# Power_Amp_carlos_2.net
KiCad netlist of a schematic drawn in EAGLE
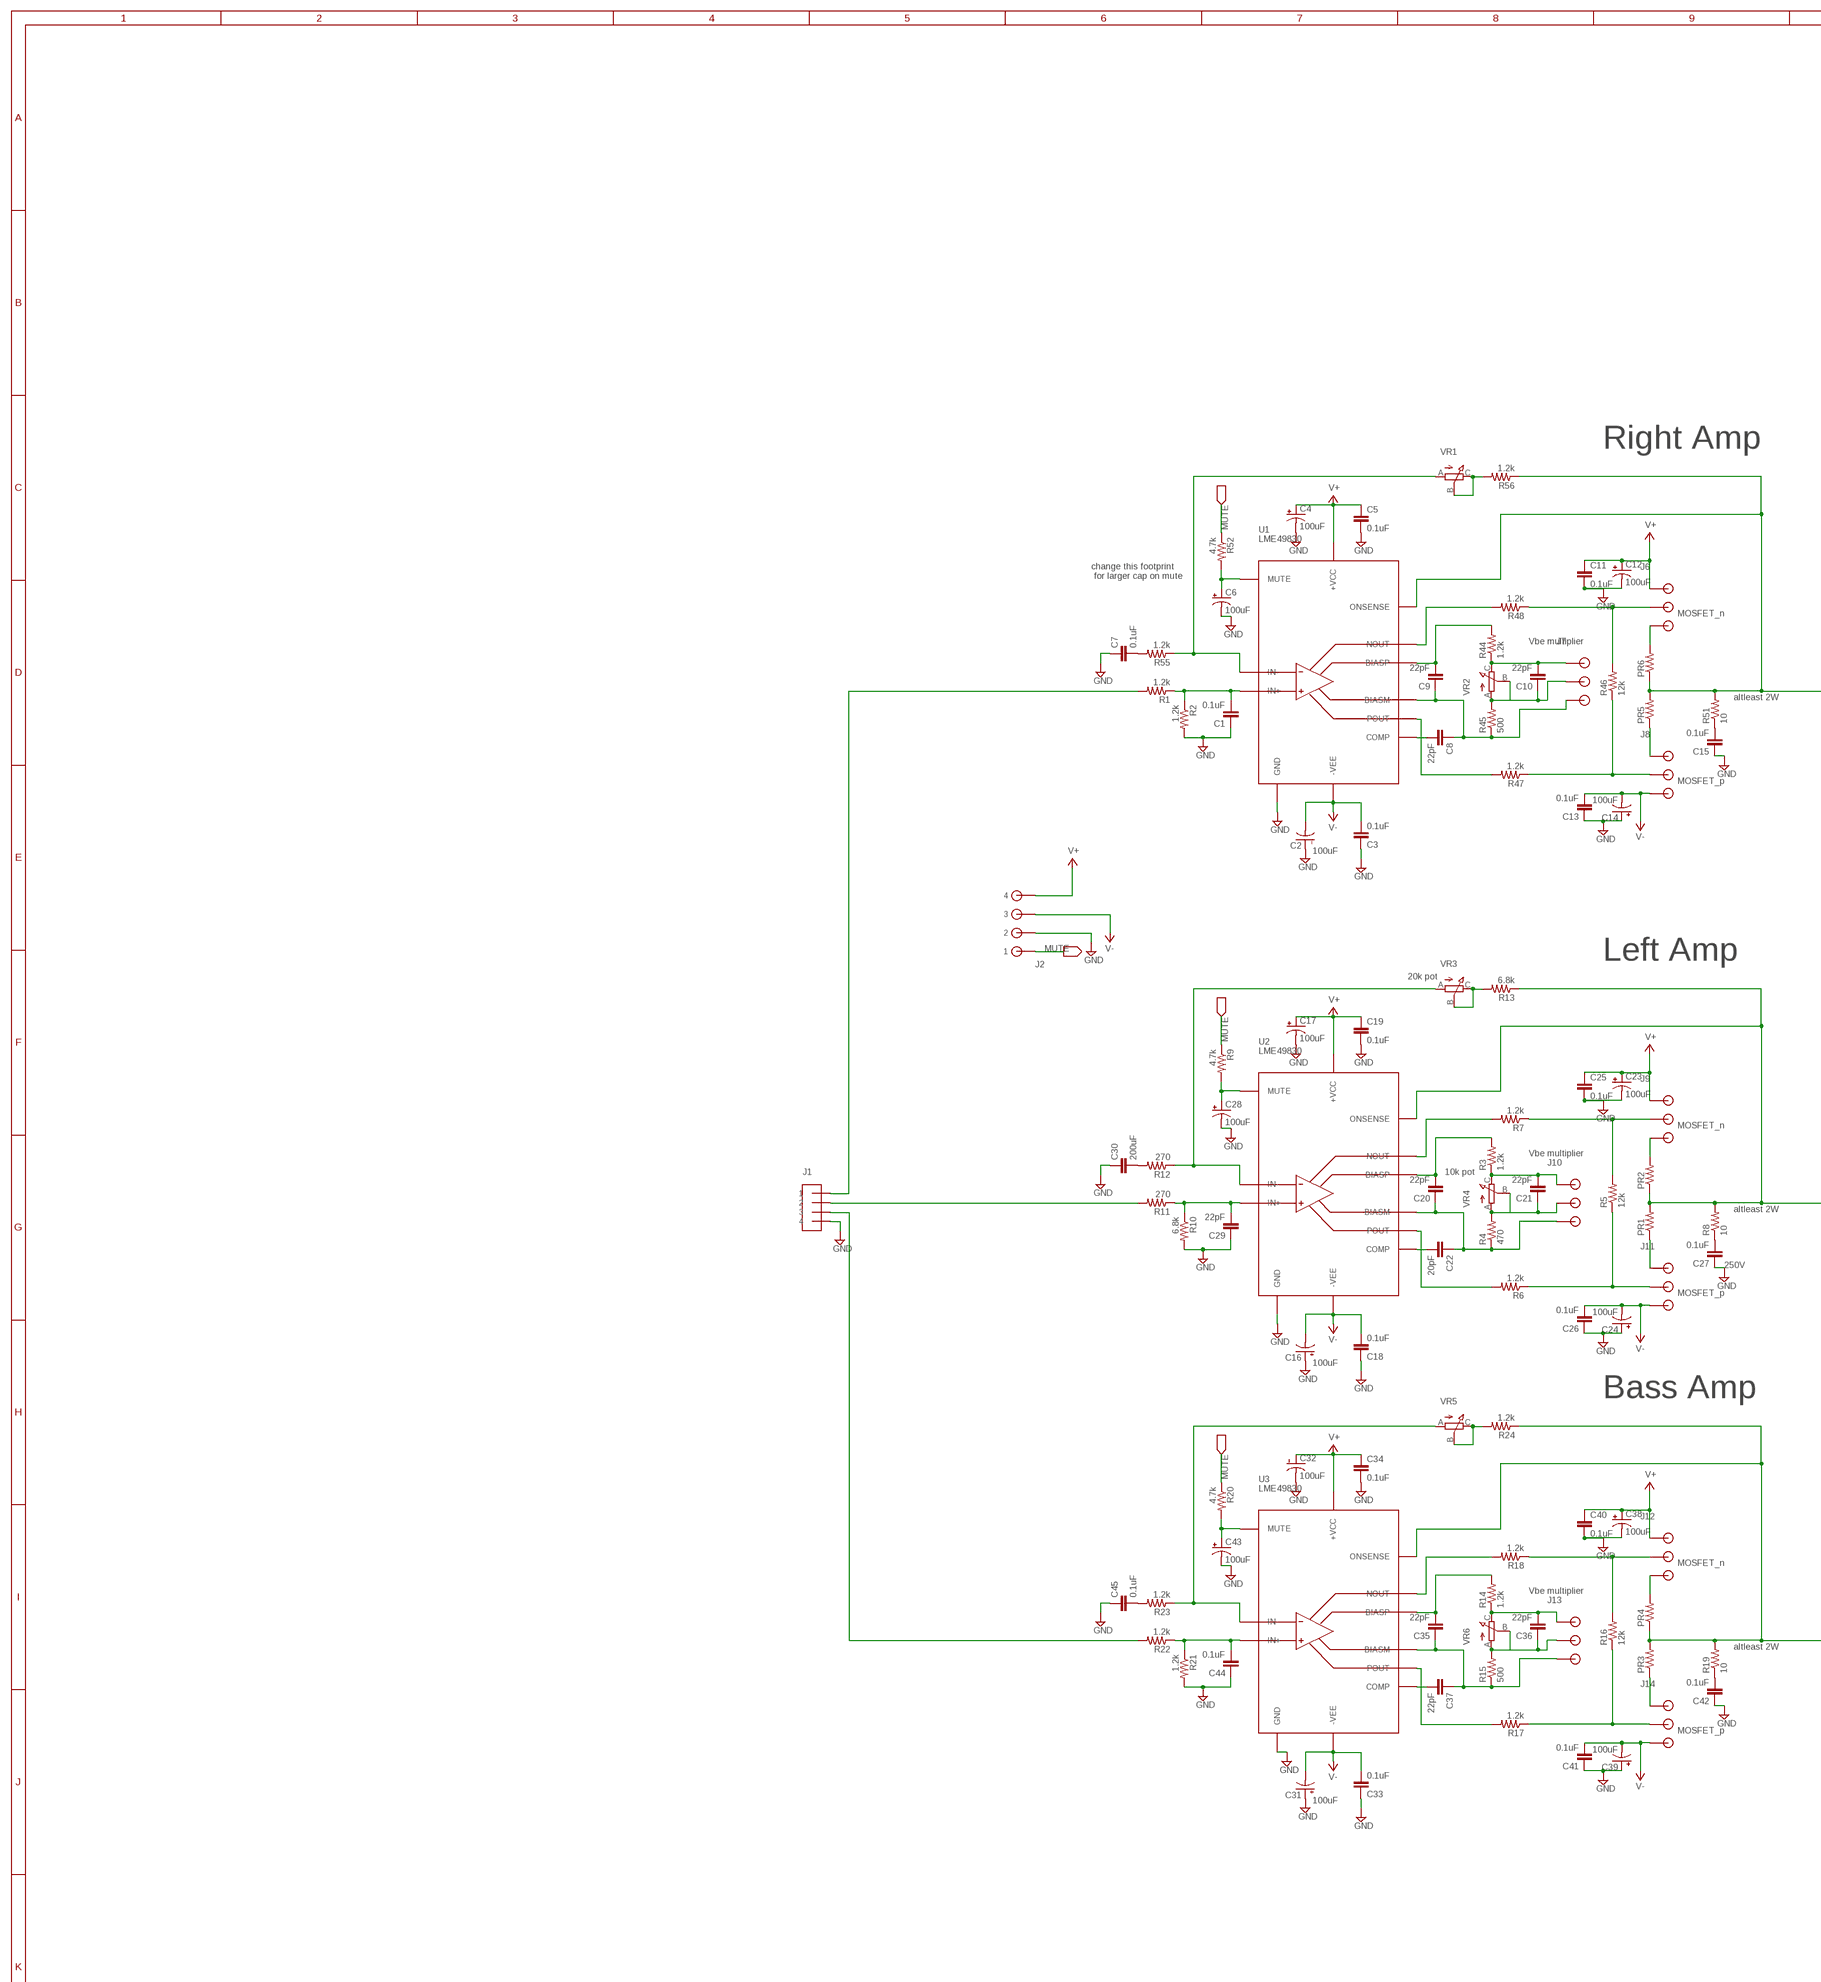
[diagram p0: schematic, sheet 1, part 1 of 3]
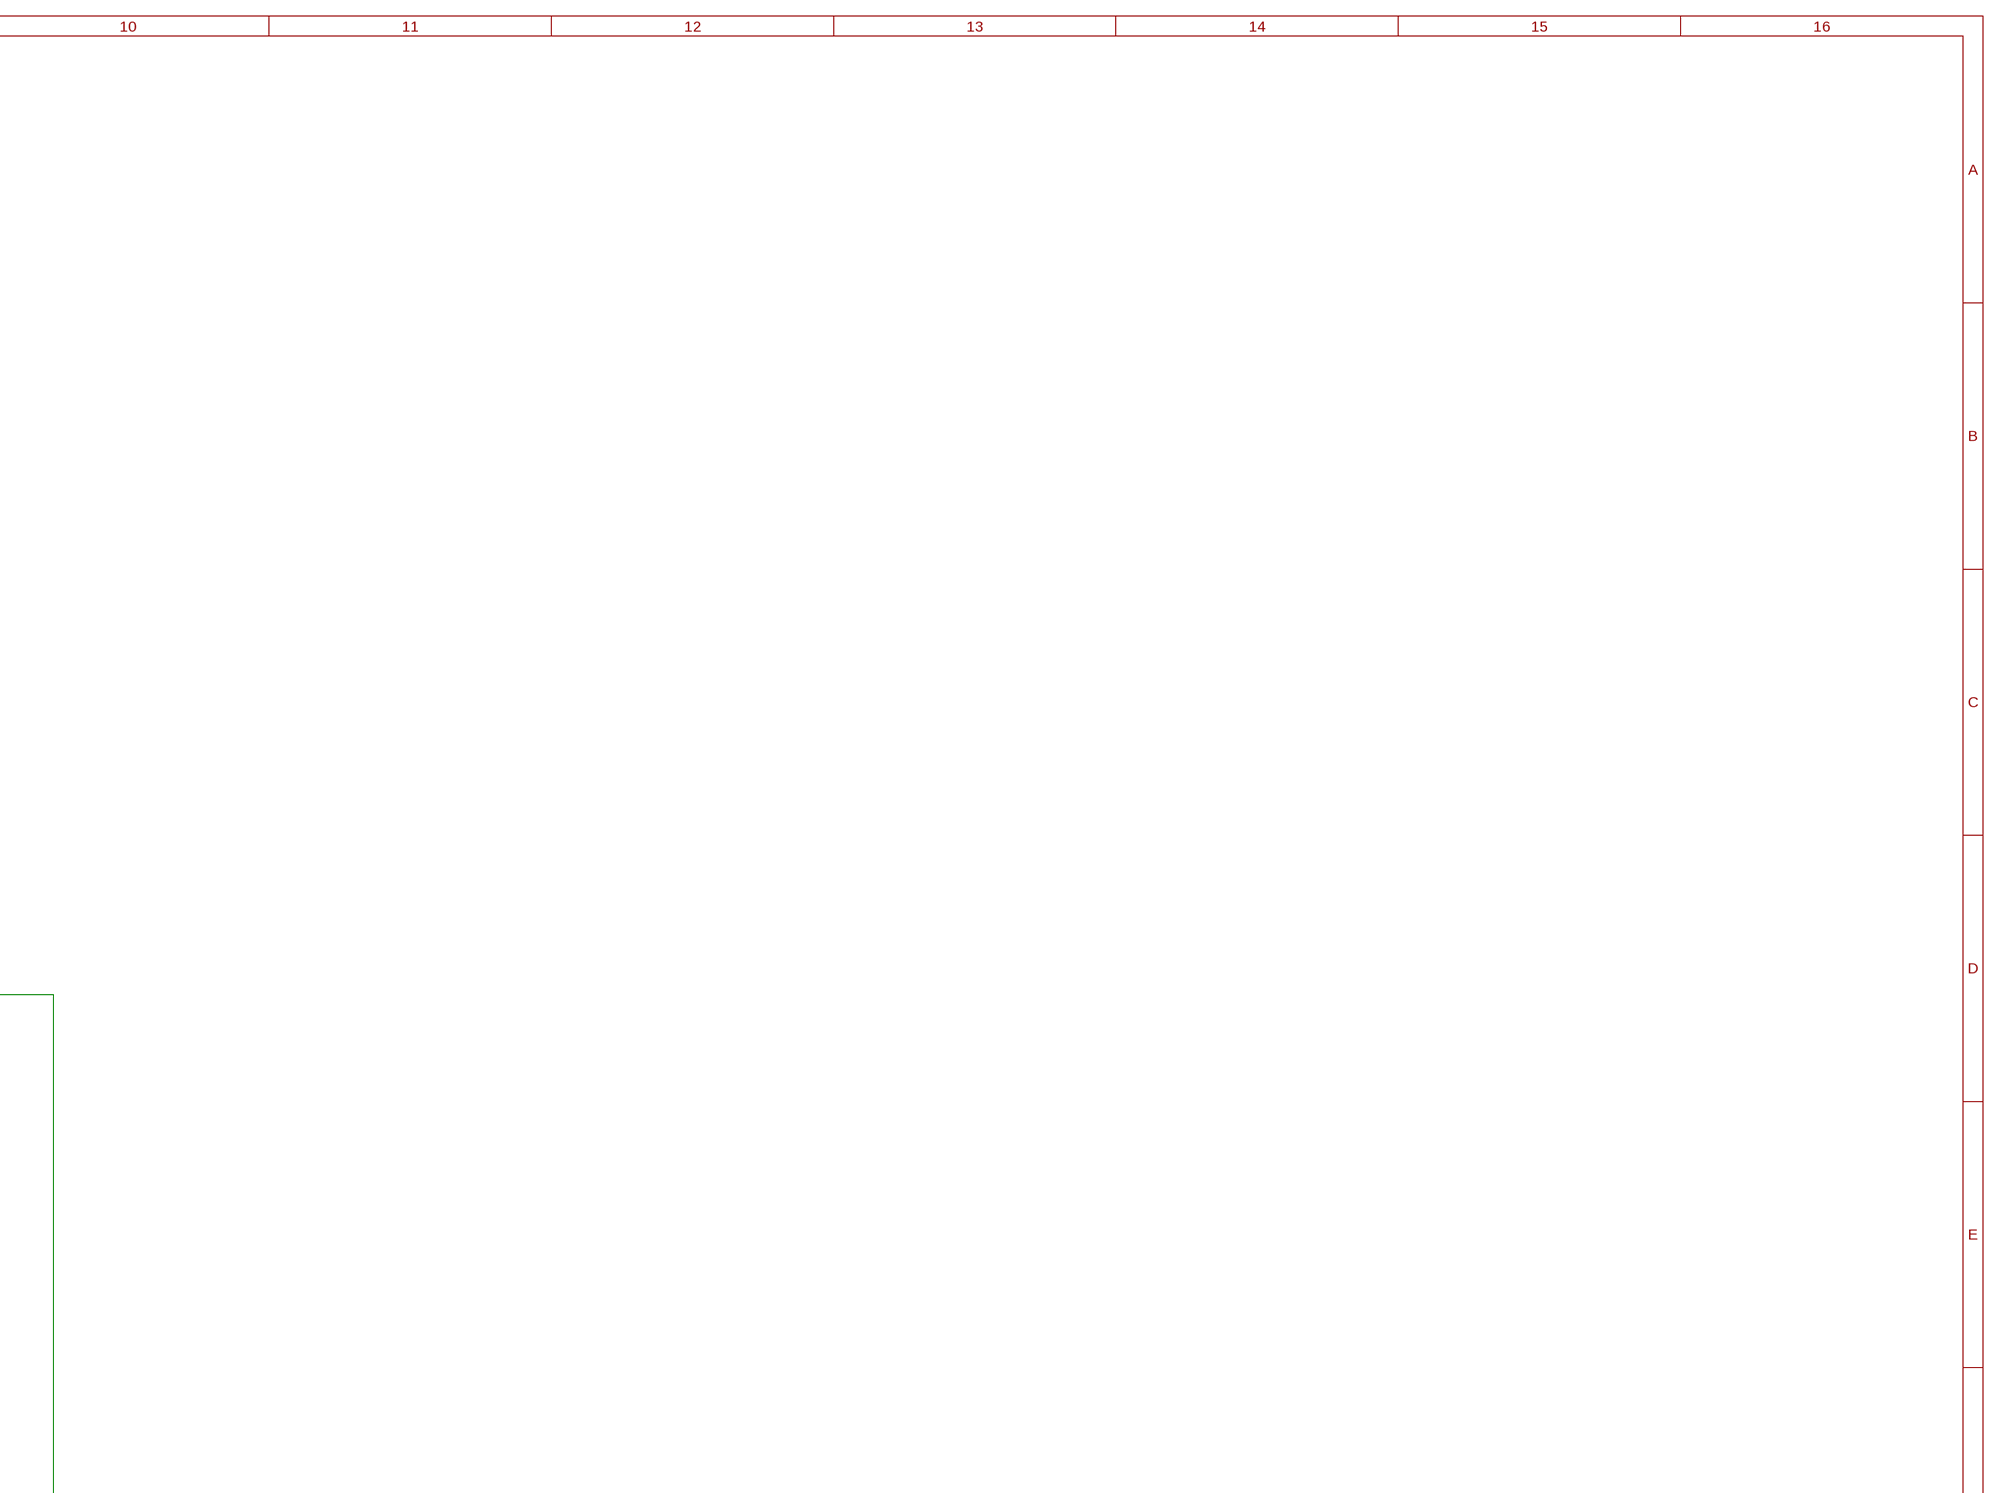
[diagram p1: schematic, sheet 1, part 2 of 3]
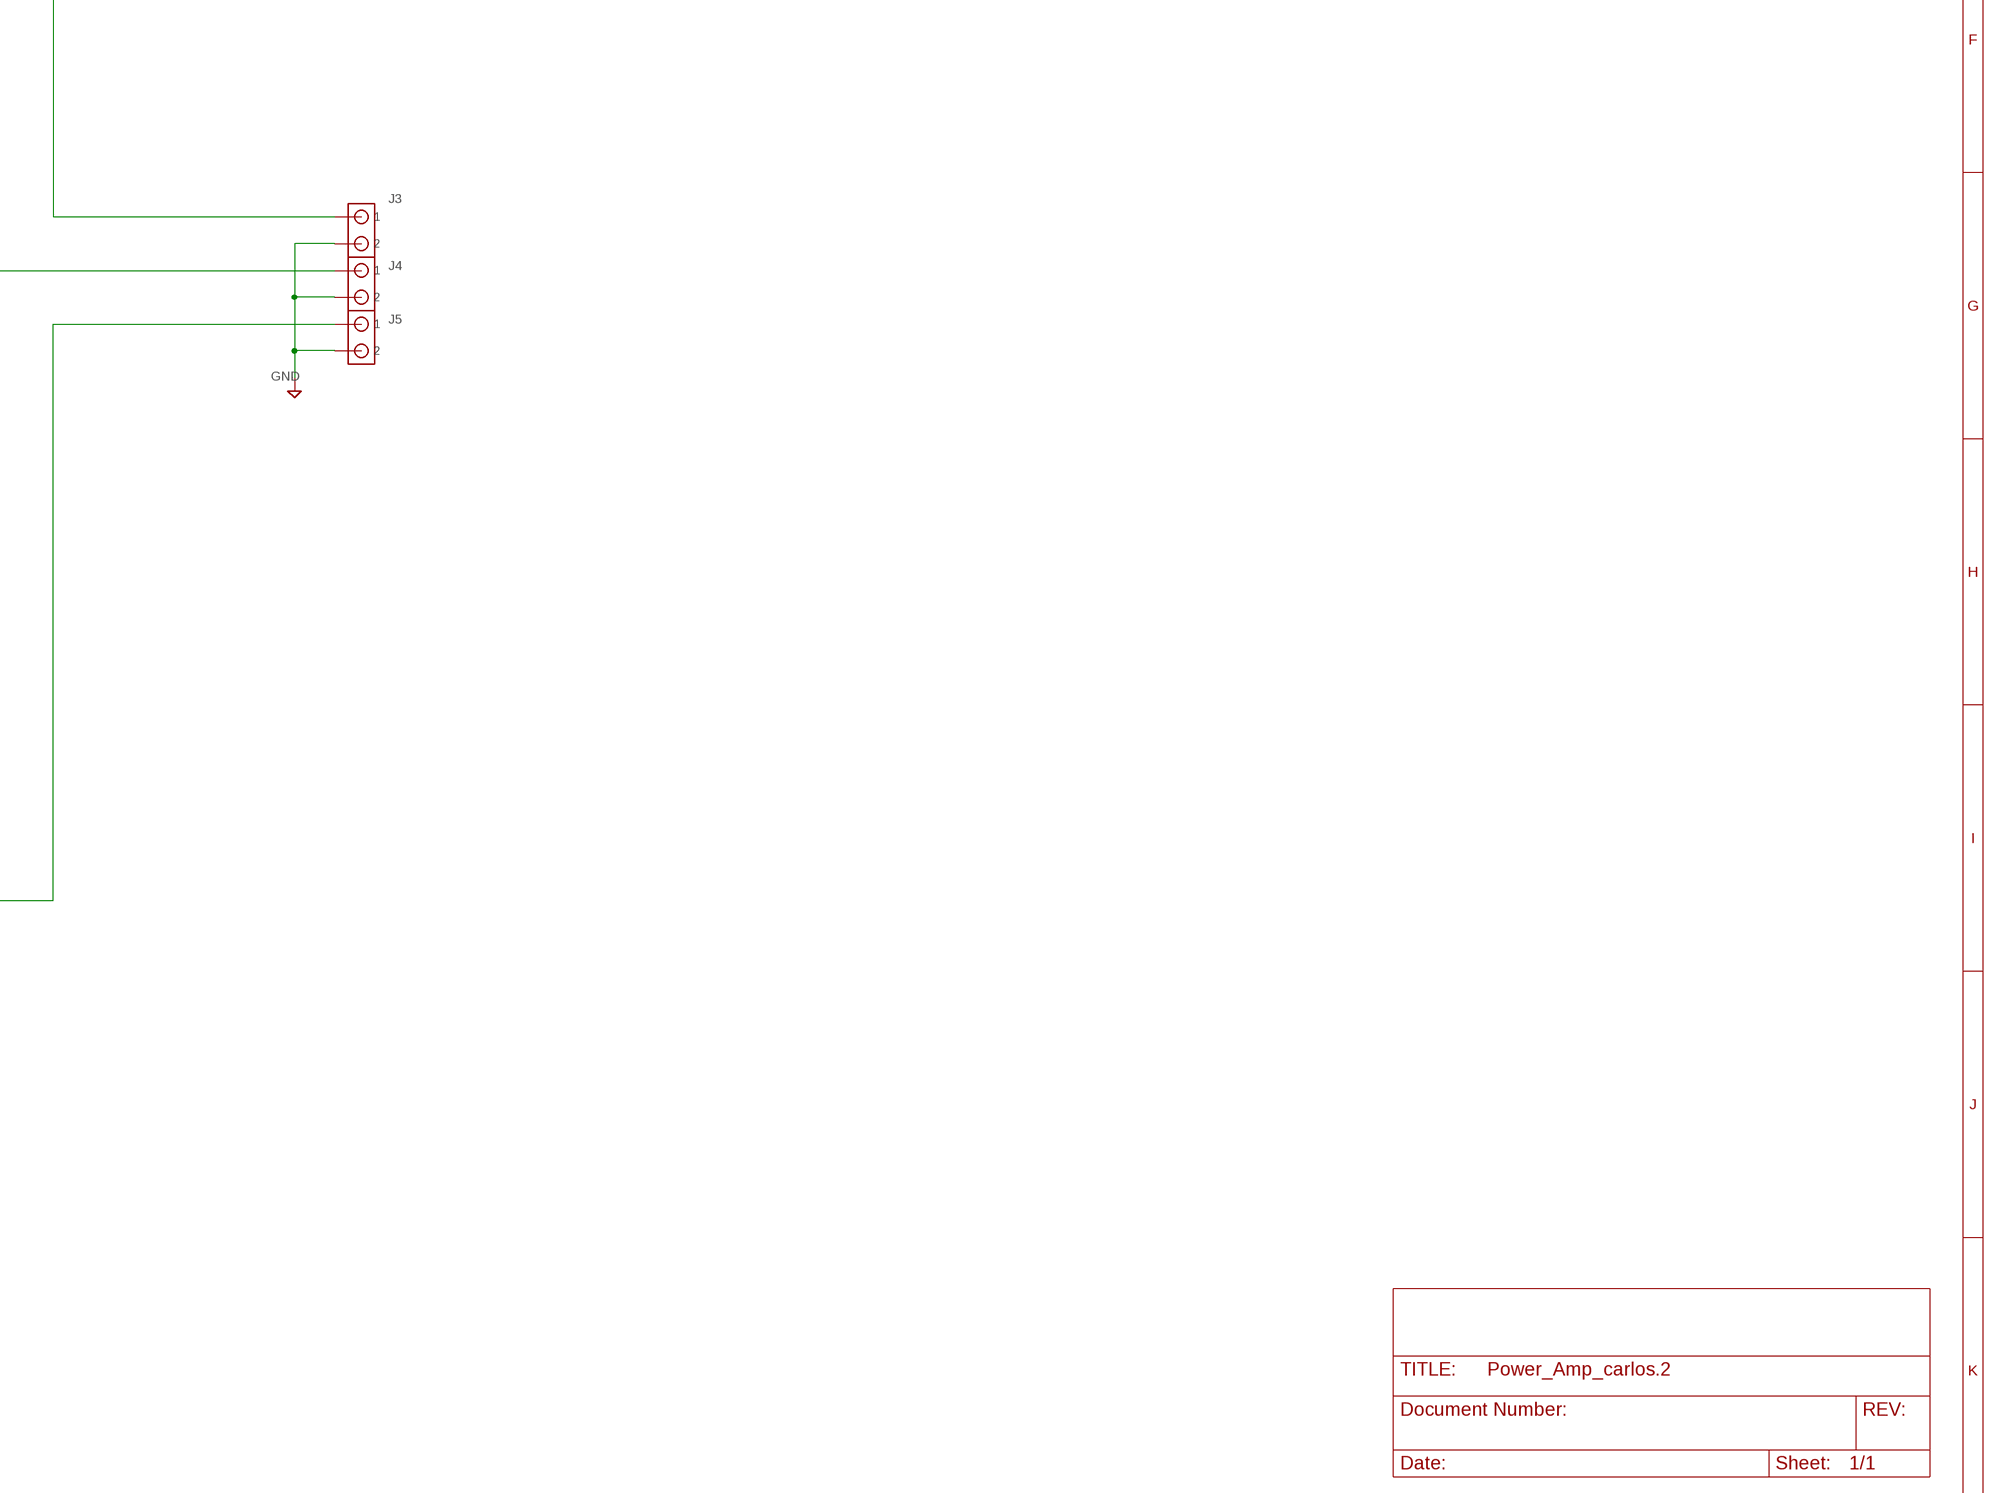
[diagram p2: schematic, sheet 1, part 3 of 3]

(export (version "E")
  (design (tool "Eeschema 10.0.6"))
  (components
    (comp (ref "C1")
      (value "0.1uF")
      (footprint "eagle-import:C050-024X044")
      (libsource (lib "eagle-import") (part "C-EU050-024X044"))
    )
    (comp (ref "C2")
      (value "100uF")
      (footprint "eagle-import:E2,5-6")
      (libsource (lib "eagle-import") (part "CPOL-USE2.5-6"))
    )
    (comp (ref "C3")
      (value "0.1uF")
      (footprint "eagle-import:C050-024X044")
      (libsource (lib "eagle-import") (part "C-EU050-024X044"))
    )
    (comp (ref "C4")
      (value "100uF")
      (footprint "eagle-import:E2,5-6")
      (libsource (lib "eagle-import") (part "CPOL-USE2.5-6"))
    )
    (comp (ref "C5")
      (value "0.1uF")
      (footprint "eagle-import:C050-024X044")
      (libsource (lib "eagle-import") (part "C-EU050-024X044"))
    )
    (comp (ref "C6")
      (value "100uF")
      (footprint "eagle-import:E2,5-6")
      (libsource (lib "eagle-import") (part "CPOL-USE2.5-6"))
    )
    (comp (ref "C7")
      (value "0.1uF")
      (footprint "eagle-import:C050-024X044")
      (libsource (lib "eagle-import") (part "C-EU050-024X044"))
    )
    (comp (ref "C8")
      (value "22pF")
      (footprint "eagle-import:C050-024X044")
      (libsource (lib "eagle-import") (part "C-EU050-024X044"))
    )
    (comp (ref "C9")
      (value "22pF")
      (footprint "eagle-import:C050-024X044")
      (libsource (lib "eagle-import") (part "C-EU050-024X044"))
    )
    (comp (ref "C10")
      (value "22pF")
      (footprint "eagle-import:C050-024X044")
      (libsource (lib "eagle-import") (part "C-EU050-024X044"))
    )
    (comp (ref "C11")
      (value "0.1uF")
      (footprint "eagle-import:C050-024X044")
      (libsource (lib "eagle-import") (part "C-EU050-024X044"))
    )
    (comp (ref "C12")
      (value "100uF")
      (footprint "eagle-import:E2,5-6")
      (libsource (lib "eagle-import") (part "CPOL-USE2.5-6"))
    )
    (comp (ref "C13")
      (value "0.1uF")
      (footprint "eagle-import:C050-024X044")
      (libsource (lib "eagle-import") (part "C-EU050-024X044"))
    )
    (comp (ref "C14")
      (value "100uF")
      (footprint "eagle-import:E2,5-6")
      (libsource (lib "eagle-import") (part "CPOL-USE2.5-6"))
    )
    (comp (ref "C15")
      (value "0.1uF")
      (footprint "eagle-import:C050-024X044")
      (libsource (lib "eagle-import") (part "C-EU050-024X044"))
    )
    (comp (ref "C16")
      (value "100uF")
      (footprint "eagle-import:E2,5-6")
      (libsource (lib "eagle-import") (part "CPOL-USE2.5-6"))
    )
    (comp (ref "C17")
      (value "100uF")
      (footprint "eagle-import:E2,5-6")
      (libsource (lib "eagle-import") (part "CPOL-USE2.5-6"))
    )
    (comp (ref "C18")
      (value "0.1uF")
      (footprint "eagle-import:C050-024X044")
      (libsource (lib "eagle-import") (part "C-EU050-024X044"))
    )
    (comp (ref "C19")
      (value "0.1uF")
      (footprint "eagle-import:C050-024X044")
      (libsource (lib "eagle-import") (part "C-EU050-024X044"))
    )
    (comp (ref "C20")
      (value "22pF")
      (footprint "eagle-import:C050-024X044")
      (libsource (lib "eagle-import") (part "C-EU050-024X044"))
    )
    (comp (ref "C21")
      (value "22pF")
      (footprint "eagle-import:C050-024X044")
      (libsource (lib "eagle-import") (part "C-EU050-024X044"))
    )
    (comp (ref "C22")
      (value "20pF")
      (footprint "eagle-import:C050-024X044")
      (libsource (lib "eagle-import") (part "C-EU050-024X044"))
    )
    (comp (ref "C23")
      (value "100uF")
      (footprint "eagle-import:E2,5-6")
      (libsource (lib "eagle-import") (part "CPOL-USE2.5-6"))
    )
    (comp (ref "C24")
      (value "100uF")
      (footprint "eagle-import:E2,5-6")
      (libsource (lib "eagle-import") (part "CPOL-USE2.5-6"))
    )
    (comp (ref "C25")
      (value "0.1uF")
      (footprint "eagle-import:C050-024X044")
      (libsource (lib "eagle-import") (part "C-EU050-024X044"))
    )
    (comp (ref "C26")
      (value "0.1uF")
      (footprint "eagle-import:C050-024X044")
      (libsource (lib "eagle-import") (part "C-EU050-024X044"))
    )
    (comp (ref "C27")
      (value "0.1uF")
      (footprint "eagle-import:C050-024X044")
      (libsource (lib "eagle-import") (part "C-EU050-024X044"))
    )
    (comp (ref "C28")
      (value "100uF")
      (footprint "eagle-import:E2,5-6")
      (libsource (lib "eagle-import") (part "CPOL-USE2.5-6"))
    )
    (comp (ref "C29")
      (value "22pF")
      (footprint "eagle-import:C050-024X044")
      (libsource (lib "eagle-import") (part "C-EU050-024X044"))
    )
    (comp (ref "C30")
      (value "200uF")
      (footprint "eagle-import:C050-024X044")
      (libsource (lib "eagle-import") (part "C-EU050-024X044"))
    )
    (comp (ref "C31")
      (value "100uF")
      (footprint "eagle-import:E2,5-6")
      (libsource (lib "eagle-import") (part "CPOL-USE2.5-6"))
    )
    (comp (ref "C32")
      (value "100uF")
      (footprint "eagle-import:E2,5-6")
      (libsource (lib "eagle-import") (part "CPOL-USE2.5-6"))
    )
    (comp (ref "C33")
      (value "0.1uF")
      (footprint "eagle-import:C050-024X044")
      (libsource (lib "eagle-import") (part "C-EU050-024X044"))
    )
    (comp (ref "C34")
      (value "0.1uF")
      (footprint "eagle-import:C050-024X044")
      (libsource (lib "eagle-import") (part "C-EU050-024X044"))
    )
    (comp (ref "C35")
      (value "22pF")
      (footprint "eagle-import:C050-024X044")
      (libsource (lib "eagle-import") (part "C-EU050-024X044"))
    )
    (comp (ref "C36")
      (value "22pF")
      (footprint "eagle-import:C050-024X044")
      (libsource (lib "eagle-import") (part "C-EU050-024X044"))
    )
    (comp (ref "C37")
      (value "22pF")
      (footprint "eagle-import:C050-024X044")
      (libsource (lib "eagle-import") (part "C-EU050-024X044"))
    )
    (comp (ref "C38")
      (value "100uF")
      (footprint "eagle-import:E2,5-6")
      (libsource (lib "eagle-import") (part "CPOL-USE2.5-6"))
    )
    (comp (ref "C39")
      (value "100uF")
      (footprint "eagle-import:E2,5-6")
      (libsource (lib "eagle-import") (part "CPOL-USE2.5-6"))
    )
    (comp (ref "C40")
      (value "0.1uF")
      (footprint "eagle-import:C050-024X044")
      (libsource (lib "eagle-import") (part "C-EU050-024X044"))
    )
    (comp (ref "C41")
      (value "0.1uF")
      (footprint "eagle-import:C050-024X044")
      (libsource (lib "eagle-import") (part "C-EU050-024X044"))
    )
    (comp (ref "C42")
      (value "0.1uF")
      (footprint "eagle-import:C050-024X044")
      (libsource (lib "eagle-import") (part "C-EU050-024X044"))
    )
    (comp (ref "C43")
      (value "100uF")
      (footprint "eagle-import:E2,5-6")
      (libsource (lib "eagle-import") (part "CPOL-USE2.5-6"))
    )
    (comp (ref "C44")
      (value "0.1uF")
      (footprint "eagle-import:C050-024X044")
      (libsource (lib "eagle-import") (part "C-EU050-024X044"))
    )
    (comp (ref "C45")
      (value "0.1uF")
      (footprint "eagle-import:C050-024X044")
      (libsource (lib "eagle-import") (part "C-EU050-024X044"))
    )
    (comp (ref "J1")
      (value "4_PIN_AMPCONN")
      (footprint "eagle-import:4_PIN_AMPCON")
      (libsource (lib "eagle-import") (part "4_PIN_AMPCONN"))
    )
    (comp (ref "J2")
      (value "1984633")
      (footprint "eagle-import:1984633")
      (libsource (lib "eagle-import") (part "1984633"))
    )
    (comp (ref "J3")
      (value "2TERMINAL_SPEAKER")
      (footprint "eagle-import:2TERMINAL_SPEAKER")
      (libsource (lib "eagle-import") (part "2TERMINAL_SPEAKER"))
    )
    (comp (ref "J4")
      (value "2TERMINAL_SPEAKER")
      (footprint "eagle-import:2TERMINAL_SPEAKER")
      (libsource (lib "eagle-import") (part "2TERMINAL_SPEAKER"))
    )
    (comp (ref "J5")
      (value "2TERMINAL_SPEAKER")
      (footprint "eagle-import:2TERMINAL_SPEAKER")
      (libsource (lib "eagle-import") (part "2TERMINAL_SPEAKER"))
    )
    (comp (ref "J6")
      (value "OSTVN03A150")
      (footprint "eagle-import:OSTVN03A150")
      (libsource (lib "eagle-import") (part "OSTVN03A150"))
    )
    (comp (ref "J7")
      (value "OSTVN03A150")
      (footprint "eagle-import:OSTVN03A150")
      (libsource (lib "eagle-import") (part "OSTVN03A150"))
    )
    (comp (ref "J8")
      (value "OSTVN03A150")
      (footprint "eagle-import:OSTVN03A150")
      (libsource (lib "eagle-import") (part "OSTVN03A150"))
    )
    (comp (ref "J9")
      (value "OSTVN03A150")
      (footprint "eagle-import:OSTVN03A150")
      (libsource (lib "eagle-import") (part "OSTVN03A150"))
    )
    (comp (ref "J10")
      (value "OSTVN03A150")
      (footprint "eagle-import:OSTVN03A150")
      (libsource (lib "eagle-import") (part "OSTVN03A150"))
    )
    (comp (ref "J11")
      (value "OSTVN03A150")
      (footprint "eagle-import:OSTVN03A150")
      (libsource (lib "eagle-import") (part "OSTVN03A150"))
    )
    (comp (ref "J12")
      (value "OSTVN03A150")
      (footprint "eagle-import:OSTVN03A150")
      (libsource (lib "eagle-import") (part "OSTVN03A150"))
    )
    (comp (ref "J13")
      (value "OSTVN03A150")
      (footprint "eagle-import:OSTVN03A150")
      (libsource (lib "eagle-import") (part "OSTVN03A150"))
    )
    (comp (ref "J14")
      (value "OSTVN03A150")
      (footprint "eagle-import:OSTVN03A150")
      (libsource (lib "eagle-import") (part "OSTVN03A150"))
    )
    (comp (ref "PR1")
      (value "R-US_0617/5V")
      (footprint "eagle-import:0617V")
      (libsource (lib "eagle-import") (part "R-US_0617/5V"))
    )
    (comp (ref "PR2")
      (value "R-US_0617/5V")
      (footprint "eagle-import:0617V")
      (libsource (lib "eagle-import") (part "R-US_0617/5V"))
    )
    (comp (ref "PR3")
      (value "R-US_0617/5V")
      (footprint "eagle-import:0617V")
      (libsource (lib "eagle-import") (part "R-US_0617/5V"))
    )
    (comp (ref "PR4")
      (value "R-US_0617/5V")
      (footprint "eagle-import:0617V")
      (libsource (lib "eagle-import") (part "R-US_0617/5V"))
    )
    (comp (ref "PR5")
      (value "R-US_0617/5V")
      (footprint "eagle-import:0617V")
      (libsource (lib "eagle-import") (part "R-US_0617/5V"))
    )
    (comp (ref "PR6")
      (value "R-US_0617/5V")
      (footprint "eagle-import:0617V")
      (libsource (lib "eagle-import") (part "R-US_0617/5V"))
    )
    (comp (ref "R1")
      (value "1.2k")
      (footprint "eagle-import:0204V")
      (libsource (lib "eagle-import") (part "R-US_0204/2V"))
    )
    (comp (ref "R2")
      (value "1.2k")
      (footprint "eagle-import:0204V")
      (libsource (lib "eagle-import") (part "R-US_0204/2V"))
    )
    (comp (ref "R3")
      (value "1.2k")
      (footprint "eagle-import:0204V")
      (libsource (lib "eagle-import") (part "R-US_0204/2V"))
    )
    (comp (ref "R4")
      (value "470")
      (footprint "eagle-import:0204V")
      (libsource (lib "eagle-import") (part "R-US_0204/2V"))
    )
    (comp (ref "R5")
      (value "12k")
      (footprint "eagle-import:0204V")
      (libsource (lib "eagle-import") (part "R-US_0204/2V"))
    )
    (comp (ref "R6")
      (value "1.2k")
      (footprint "eagle-import:0204V")
      (libsource (lib "eagle-import") (part "R-US_0204/2V"))
    )
    (comp (ref "R7")
      (value "1.2k")
      (footprint "eagle-import:0204V")
      (libsource (lib "eagle-import") (part "R-US_0204/2V"))
    )
    (comp (ref "R8")
      (value "10")
      (footprint "eagle-import:0617V")
      (libsource (lib "eagle-import") (part "R-US_0617/5V"))
    )
    (comp (ref "R9")
      (value "4.7k")
      (footprint "eagle-import:0204V")
      (libsource (lib "eagle-import") (part "R-US_0204/2V"))
    )
    (comp (ref "R10")
      (value "6.8k")
      (footprint "eagle-import:0204V")
      (libsource (lib "eagle-import") (part "R-US_0204/2V"))
    )
    (comp (ref "R11")
      (value "270")
      (footprint "eagle-import:0204V")
      (libsource (lib "eagle-import") (part "R-US_0204/2V"))
    )
    (comp (ref "R12")
      (value "270")
      (footprint "eagle-import:0204V")
      (libsource (lib "eagle-import") (part "R-US_0204/2V"))
    )
    (comp (ref "R13")
      (value "6.8k")
      (footprint "eagle-import:0204V")
      (libsource (lib "eagle-import") (part "R-US_0204/2V"))
    )
    (comp (ref "R14")
      (value "1.2k")
      (footprint "eagle-import:0204V")
      (libsource (lib "eagle-import") (part "R-US_0204/2V"))
    )
    (comp (ref "R15")
      (value "500")
      (footprint "eagle-import:0204V")
      (libsource (lib "eagle-import") (part "R-US_0204/2V"))
    )
    (comp (ref "R16")
      (value "12k")
      (footprint "eagle-import:0204V")
      (libsource (lib "eagle-import") (part "R-US_0204/2V"))
    )
    (comp (ref "R17")
      (value "1.2k")
      (footprint "eagle-import:0204V")
      (libsource (lib "eagle-import") (part "R-US_0204/2V"))
    )
    (comp (ref "R18")
      (value "1.2k")
      (footprint "eagle-import:0204V")
      (libsource (lib "eagle-import") (part "R-US_0204/2V"))
    )
    (comp (ref "R19")
      (value "10")
      (footprint "eagle-import:0617V")
      (libsource (lib "eagle-import") (part "R-US_0617/5V"))
    )
    (comp (ref "R20")
      (value "4.7k")
      (footprint "eagle-import:0204V")
      (libsource (lib "eagle-import") (part "R-US_0204/2V"))
    )
    (comp (ref "R21")
      (value "1.2k")
      (footprint "eagle-import:0204V")
      (libsource (lib "eagle-import") (part "R-US_0204/2V"))
    )
    (comp (ref "R22")
      (value "1.2k")
      (footprint "eagle-import:0204V")
      (libsource (lib "eagle-import") (part "R-US_0204/2V"))
    )
    (comp (ref "R23")
      (value "1.2k")
      (footprint "eagle-import:0204V")
      (libsource (lib "eagle-import") (part "R-US_0204/2V"))
    )
    (comp (ref "R24")
      (value "1.2k")
      (footprint "eagle-import:0204V")
      (libsource (lib "eagle-import") (part "R-US_0204/2V"))
    )
    (comp (ref "R44")
      (value "1.2k")
      (footprint "eagle-import:0204V")
      (libsource (lib "eagle-import") (part "R-US_0204/2V"))
    )
    (comp (ref "R45")
      (value "500")
      (footprint "eagle-import:0204V")
      (libsource (lib "eagle-import") (part "R-US_0204/2V"))
    )
    (comp (ref "R46")
      (value "12k")
      (footprint "eagle-import:0204V")
      (libsource (lib "eagle-import") (part "R-US_0204/2V"))
    )
    (comp (ref "R47")
      (value "1.2k")
      (footprint "eagle-import:0204V")
      (libsource (lib "eagle-import") (part "R-US_0204/2V"))
    )
    (comp (ref "R48")
      (value "1.2k")
      (footprint "eagle-import:0204V")
      (libsource (lib "eagle-import") (part "R-US_0204/2V"))
    )
    (comp (ref "R51")
      (value "10")
      (footprint "eagle-import:0617V")
      (libsource (lib "eagle-import") (part "R-US_0617/5V"))
    )
    (comp (ref "R52")
      (value "4.7k")
      (footprint "eagle-import:0204V")
      (libsource (lib "eagle-import") (part "R-US_0204/2V"))
    )
    (comp (ref "R55")
      (value "1.2k")
      (footprint "eagle-import:0204V")
      (libsource (lib "eagle-import") (part "R-US_0204/2V"))
    )
    (comp (ref "R56")
      (value "1.2k")
      (footprint "eagle-import:0204V")
      (libsource (lib "eagle-import") (part "R-US_0204/2V"))
    )
    (comp (ref "U1")
      (value "LME49830")
      (footprint "eagle-import:NDN0015A")
      (libsource (lib "eagle-import") (part "LME49830"))
    )
    (comp (ref "U2")
      (value "LME49830")
      (footprint "eagle-import:NDN0015A")
      (libsource (lib "eagle-import") (part "LME49830"))
    )
    (comp (ref "U3")
      (value "LME49830")
      (footprint "eagle-import:NDN0015A")
      (libsource (lib "eagle-import") (part "LME49830"))
    )
    (comp (ref "VR1")
      (value "EVM2W")
      (footprint "eagle-import:EVM2W")
      (libsource (lib "eagle-import") (part "EVM2W"))
    )
    (comp (ref "VR2")
      (value "EVM2W")
      (footprint "eagle-import:EVM2W")
      (libsource (lib "eagle-import") (part "EVM2W"))
    )
    (comp (ref "VR3")
      (value "EVM2W")
      (footprint "eagle-import:EVM2W")
      (libsource (lib "eagle-import") (part "EVM2W"))
    )
    (comp (ref "VR4")
      (value "EVM2W")
      (footprint "eagle-import:EVM2W")
      (libsource (lib "eagle-import") (part "EVM2W"))
    )
    (comp (ref "VR5")
      (value "EVM2W")
      (footprint "eagle-import:EVM2W")
      (libsource (lib "eagle-import") (part "EVM2W"))
    )
    (comp (ref "VR6")
      (value "EVM2W")
      (footprint "eagle-import:EVM2W")
      (libsource (lib "eagle-import") (part "EVM2W"))
    )
  )
  (nets
    (net (code "1") (name "/MUTE") (class "Default")
      (node (ref "J2") (pin "P$1") (pinfunction "1_P$1") (pintype "passive"))
      (node (ref "R20") (pin "1") (pinfunction "1_1") (pintype "passive"))
      (node (ref "R52") (pin "1") (pinfunction "1_1") (pintype "passive"))
      (node (ref "R9") (pin "1") (pinfunction "1_1") (pintype "passive"))
    )
    (net (code "2") (name "GND") (class "Default")
      (node (ref "C1") (pin "1") (pinfunction "1_1") (pintype "passive"))
      (node (ref "C11") (pin "2") (pinfunction "2_2") (pintype "passive"))
      (node (ref "C12") (pin "-") (pinfunction "-_-") (pintype "passive"))
      (node (ref "C13") (pin "1") (pinfunction "1_1") (pintype "passive"))
      (node (ref "C14") (pin "+") (pinfunction "+_+") (pintype "passive"))
      (node (ref "C15") (pin "1") (pinfunction "1_1") (pintype "passive"))
      (node (ref "C16") (pin "+") (pinfunction "+_+") (pintype "passive"))
      (node (ref "C17") (pin "-") (pinfunction "-_-") (pintype "passive"))
      (node (ref "C18") (pin "1") (pinfunction "1_1") (pintype "passive"))
      (node (ref "C19") (pin "2") (pinfunction "2_2") (pintype "passive"))
      (node (ref "C2") (pin "+") (pinfunction "+_+") (pintype "passive"))
      (node (ref "C23") (pin "-") (pinfunction "-_-") (pintype "passive"))
      (node (ref "C24") (pin "+") (pinfunction "+_+") (pintype "passive"))
      (node (ref "C25") (pin "2") (pinfunction "2_2") (pintype "passive"))
      (node (ref "C26") (pin "1") (pinfunction "1_1") (pintype "passive"))
      (node (ref "C27") (pin "1") (pinfunction "1_1") (pintype "passive"))
      (node (ref "C28") (pin "-") (pinfunction "-_-") (pintype "passive"))
      (node (ref "C29") (pin "1") (pinfunction "1_1") (pintype "passive"))
      (node (ref "C3") (pin "1") (pinfunction "1_1") (pintype "passive"))
      (node (ref "C30") (pin "1") (pinfunction "1_1") (pintype "passive"))
      (node (ref "C31") (pin "+") (pinfunction "+_+") (pintype "passive"))
      (node (ref "C32") (pin "-") (pinfunction "-_-") (pintype "passive"))
      (node (ref "C33") (pin "1") (pinfunction "1_1") (pintype "passive"))
      (node (ref "C34") (pin "2") (pinfunction "2_2") (pintype "passive"))
      (node (ref "C38") (pin "-") (pinfunction "-_-") (pintype "passive"))
      (node (ref "C39") (pin "+") (pinfunction "+_+") (pintype "passive"))
      (node (ref "C4") (pin "-") (pinfunction "-_-") (pintype "passive"))
      (node (ref "C40") (pin "2") (pinfunction "2_2") (pintype "passive"))
      (node (ref "C41") (pin "1") (pinfunction "1_1") (pintype "passive"))
      (node (ref "C42") (pin "1") (pinfunction "1_1") (pintype "passive"))
      (node (ref "C43") (pin "-") (pinfunction "-_-") (pintype "passive"))
      (node (ref "C44") (pin "1") (pinfunction "1_1") (pintype "passive"))
      (node (ref "C45") (pin "1") (pinfunction "1_1") (pintype "passive"))
      (node (ref "C5") (pin "2") (pinfunction "2_2") (pintype "passive"))
      (node (ref "C6") (pin "-") (pinfunction "-_-") (pintype "passive"))
      (node (ref "C7") (pin "1") (pinfunction "1_1") (pintype "passive"))
      (node (ref "J1") (pin "4") (pinfunction "4_4") (pintype "passive"))
      (node (ref "J2") (pin "P$2") (pinfunction "2_P$2") (pintype "passive"))
      (node (ref "J3") (pin "P$2") (pinfunction "2_P$2") (pintype "passive"))
      (node (ref "J4") (pin "P$2") (pinfunction "2_P$2") (pintype "passive"))
      (node (ref "J5") (pin "P$2") (pinfunction "2_P$2") (pintype "passive"))
      (node (ref "R10") (pin "2") (pinfunction "2_2") (pintype "passive"))
      (node (ref "R2") (pin "2") (pinfunction "2_2") (pintype "passive"))
      (node (ref "R21") (pin "2") (pinfunction "2_2") (pintype "passive"))
      (node (ref "U1") (pin "P3") (pinfunction "GND_P3") (pintype "bidirectional"))
      (node (ref "U2") (pin "P3") (pinfunction "GND_P3") (pintype "bidirectional"))
      (node (ref "U3") (pin "P3") (pinfunction "GND_P3") (pintype "bidirectional"))
    )
    (net (code "3") (name "Net-(C7-Pad2)") (class "Default")
      (node (ref "C7") (pin "2") (pinfunction "2_2") (pintype "passive"))
      (node (ref "R55") (pin "2") (pinfunction "2_2") (pintype "passive"))
    )
    (net (code "4") (name "Net-(C15-Pad2)") (class "Default")
      (node (ref "C15") (pin "2") (pinfunction "2_2") (pintype "passive"))
      (node (ref "R51") (pin "1") (pinfunction "1_1") (pintype "passive"))
    )
    (net (code "5") (name "Net-(C27-Pad2)") (class "Default")
      (node (ref "C27") (pin "2") (pinfunction "2_2") (pintype "passive"))
      (node (ref "R8") (pin "1") (pinfunction "1_1") (pintype "passive"))
    )
    (net (code "6") (name "Net-(C30-Pad2)") (class "Default")
      (node (ref "C30") (pin "2") (pinfunction "2_2") (pintype "passive"))
      (node (ref "R12") (pin "2") (pinfunction "2_2") (pintype "passive"))
    )
    (net (code "7") (name "Net-(C42-Pad2)") (class "Default")
      (node (ref "C42") (pin "2") (pinfunction "2_2") (pintype "passive"))
      (node (ref "R19") (pin "1") (pinfunction "1_1") (pintype "passive"))
    )
    (net (code "8") (name "Net-(C45-Pad2)") (class "Default")
      (node (ref "C45") (pin "2") (pinfunction "2_2") (pintype "passive"))
      (node (ref "R23") (pin "2") (pinfunction "2_2") (pintype "passive"))
    )
    (net (code "9") (name "Net-(J1-Pad1)") (class "Default")
      (node (ref "J1") (pin "1") (pinfunction "1_1") (pintype "passive"))
      (node (ref "R1") (pin "2") (pinfunction "2_2") (pintype "passive"))
    )
    (net (code "10") (name "Net-(J1-Pad2)") (class "Default")
      (node (ref "J1") (pin "2") (pinfunction "2_2") (pintype "passive"))
      (node (ref "R11") (pin "2") (pinfunction "2_2") (pintype "passive"))
    )
    (net (code "11") (name "Net-(J1-Pad3)") (class "Default")
      (node (ref "J1") (pin "3") (pinfunction "3_3") (pintype "passive"))
      (node (ref "R22") (pin "2") (pinfunction "2_2") (pintype "passive"))
    )
    (net (code "12") (name "Net-(J3-1)") (class "Default")
      (node (ref "J3") (pin "P$1") (pinfunction "1_P$1") (pintype "passive"))
      (node (ref "PR5") (pin "2") (pinfunction "2_2") (pintype "passive"))
      (node (ref "PR6") (pin "1") (pinfunction "1_1") (pintype "passive"))
      (node (ref "R51") (pin "2") (pinfunction "2_2") (pintype "passive"))
      (node (ref "R56") (pin "1") (pinfunction "1_1") (pintype "passive"))
      (node (ref "U1") (pin "P$8") (pinfunction "ONSENSE_P$8") (pintype "bidirectional"))
    )
    (net (code "13") (name "Net-(J4-1)") (class "Default")
      (node (ref "J4") (pin "P$1") (pinfunction "1_P$1") (pintype "passive"))
      (node (ref "PR1") (pin "2") (pinfunction "2_2") (pintype "passive"))
      (node (ref "PR2") (pin "1") (pinfunction "1_1") (pintype "passive"))
      (node (ref "R13") (pin "1") (pinfunction "1_1") (pintype "passive"))
      (node (ref "R8") (pin "2") (pinfunction "2_2") (pintype "passive"))
      (node (ref "U2") (pin "P$8") (pinfunction "ONSENSE_P$8") (pintype "bidirectional"))
    )
    (net (code "14") (name "Net-(J5-1)") (class "Default")
      (node (ref "J5") (pin "P$1") (pinfunction "1_P$1") (pintype "passive"))
      (node (ref "PR3") (pin "2") (pinfunction "2_2") (pintype "passive"))
      (node (ref "PR4") (pin "1") (pinfunction "1_1") (pintype "passive"))
      (node (ref "R19") (pin "2") (pinfunction "2_2") (pintype "passive"))
      (node (ref "R24") (pin "1") (pinfunction "1_1") (pintype "passive"))
      (node (ref "U3") (pin "P$8") (pinfunction "ONSENSE_P$8") (pintype "bidirectional"))
    )
    (net (code "15") (name "Net-(J6-2)") (class "Default")
      (node (ref "J6") (pin "P$2") (pinfunction "2_P$2") (pintype "bidirectional"))
      (node (ref "R46") (pin "2") (pinfunction "2_2") (pintype "passive"))
      (node (ref "R48") (pin "1") (pinfunction "1_1") (pintype "passive"))
    )
    (net (code "16") (name "Net-(J6-3)") (class "Default")
      (node (ref "J6") (pin "P$3") (pinfunction "3_P$3") (pintype "bidirectional"))
      (node (ref "PR6") (pin "2") (pinfunction "2_2") (pintype "passive"))
    )
    (net (code "17") (name "Net-(J7-1)") (class "Default")
      (node (ref "C10") (pin "2") (pinfunction "2_2") (pintype "passive"))
      (node (ref "J7") (pin "P$1") (pinfunction "1_P$1") (pintype "bidirectional"))
      (node (ref "R44") (pin "1") (pinfunction "1_1") (pintype "passive"))
      (node (ref "VR2") (pin "C") (pinfunction "C_C") (pintype "passive"))
    )
    (net (code "18") (name "Net-(J7-2)") (class "Default")
      (node (ref "C10") (pin "1") (pinfunction "1_1") (pintype "passive"))
      (node (ref "J7") (pin "P$2") (pinfunction "2_P$2") (pintype "bidirectional"))
      (node (ref "R45") (pin "2") (pinfunction "2_2") (pintype "passive"))
      (node (ref "VR2") (pin "A") (pinfunction "A_A") (pintype "passive"))
      (node (ref "VR2") (pin "B") (pinfunction "B_B") (pintype "passive"))
    )
    (net (code "19") (name "Net-(J7-3)") (class "Default")
      (node (ref "C8") (pin "1") (pinfunction "1_1") (pintype "passive"))
      (node (ref "C9") (pin "1") (pinfunction "1_1") (pintype "passive"))
      (node (ref "J7") (pin "P$3") (pinfunction "3_P$3") (pintype "bidirectional"))
      (node (ref "R45") (pin "1") (pinfunction "1_1") (pintype "passive"))
      (node (ref "U1") (pin "P11") (pinfunction "BIASM_P11") (pintype "bidirectional"))
    )
    (net (code "20") (name "Net-(J8-1)") (class "Default")
      (node (ref "J8") (pin "P$1") (pinfunction "1_P$1") (pintype "bidirectional"))
      (node (ref "PR5") (pin "1") (pinfunction "1_1") (pintype "passive"))
    )
    (net (code "21") (name "Net-(J8-2)") (class "Default")
      (node (ref "J8") (pin "P$2") (pinfunction "2_P$2") (pintype "bidirectional"))
      (node (ref "R46") (pin "1") (pinfunction "1_1") (pintype "passive"))
      (node (ref "R47") (pin "1") (pinfunction "1_1") (pintype "passive"))
    )
    (net (code "22") (name "Net-(J9-2)") (class "Default")
      (node (ref "J9") (pin "P$2") (pinfunction "2_P$2") (pintype "bidirectional"))
      (node (ref "R5") (pin "2") (pinfunction "2_2") (pintype "passive"))
      (node (ref "R7") (pin "1") (pinfunction "1_1") (pintype "passive"))
    )
    (net (code "23") (name "Net-(J9-3)") (class "Default")
      (node (ref "J9") (pin "P$3") (pinfunction "3_P$3") (pintype "bidirectional"))
      (node (ref "PR2") (pin "2") (pinfunction "2_2") (pintype "passive"))
    )
    (net (code "24") (name "Net-(J10-1)") (class "Default")
      (node (ref "C21") (pin "2") (pinfunction "2_2") (pintype "passive"))
      (node (ref "J10") (pin "P$1") (pinfunction "1_P$1") (pintype "bidirectional"))
      (node (ref "R3") (pin "1") (pinfunction "1_1") (pintype "passive"))
      (node (ref "VR4") (pin "C") (pinfunction "C_C") (pintype "passive"))
    )
    (net (code "25") (name "Net-(J10-2)") (class "Default")
      (node (ref "C21") (pin "1") (pinfunction "1_1") (pintype "passive"))
      (node (ref "J10") (pin "P$2") (pinfunction "2_P$2") (pintype "bidirectional"))
      (node (ref "R4") (pin "2") (pinfunction "2_2") (pintype "passive"))
      (node (ref "VR4") (pin "A") (pinfunction "A_A") (pintype "passive"))
      (node (ref "VR4") (pin "B") (pinfunction "B_B") (pintype "passive"))
    )
    (net (code "26") (name "Net-(J10-3)") (class "Default")
      (node (ref "C20") (pin "1") (pinfunction "1_1") (pintype "passive"))
      (node (ref "C22") (pin "1") (pinfunction "1_1") (pintype "passive"))
      (node (ref "J10") (pin "P$3") (pinfunction "3_P$3") (pintype "bidirectional"))
      (node (ref "R4") (pin "1") (pinfunction "1_1") (pintype "passive"))
      (node (ref "U2") (pin "P11") (pinfunction "BIASM_P11") (pintype "bidirectional"))
    )
    (net (code "27") (name "Net-(J11-1)") (class "Default")
      (node (ref "J11") (pin "P$1") (pinfunction "1_P$1") (pintype "bidirectional"))
      (node (ref "PR1") (pin "1") (pinfunction "1_1") (pintype "passive"))
    )
    (net (code "28") (name "Net-(J11-2)") (class "Default")
      (node (ref "J11") (pin "P$2") (pinfunction "2_P$2") (pintype "bidirectional"))
      (node (ref "R5") (pin "1") (pinfunction "1_1") (pintype "passive"))
      (node (ref "R6") (pin "1") (pinfunction "1_1") (pintype "passive"))
    )
    (net (code "29") (name "Net-(J12-2)") (class "Default")
      (node (ref "J12") (pin "P$2") (pinfunction "2_P$2") (pintype "bidirectional"))
      (node (ref "R16") (pin "2") (pinfunction "2_2") (pintype "passive"))
      (node (ref "R18") (pin "1") (pinfunction "1_1") (pintype "passive"))
    )
    (net (code "30") (name "Net-(J12-3)") (class "Default")
      (node (ref "J12") (pin "P$3") (pinfunction "3_P$3") (pintype "bidirectional"))
      (node (ref "PR4") (pin "2") (pinfunction "2_2") (pintype "passive"))
    )
    (net (code "31") (name "Net-(J13-1)") (class "Default")
      (node (ref "C36") (pin "2") (pinfunction "2_2") (pintype "passive"))
      (node (ref "J13") (pin "P$1") (pinfunction "1_P$1") (pintype "bidirectional"))
      (node (ref "R14") (pin "1") (pinfunction "1_1") (pintype "passive"))
      (node (ref "VR6") (pin "C") (pinfunction "C_C") (pintype "passive"))
    )
    (net (code "32") (name "Net-(J13-2)") (class "Default")
      (node (ref "C36") (pin "1") (pinfunction "1_1") (pintype "passive"))
      (node (ref "J13") (pin "P$2") (pinfunction "2_P$2") (pintype "bidirectional"))
      (node (ref "R15") (pin "2") (pinfunction "2_2") (pintype "passive"))
      (node (ref "VR6") (pin "A") (pinfunction "A_A") (pintype "passive"))
      (node (ref "VR6") (pin "B") (pinfunction "B_B") (pintype "passive"))
    )
    (net (code "33") (name "Net-(J13-3)") (class "Default")
      (node (ref "C35") (pin "1") (pinfunction "1_1") (pintype "passive"))
      (node (ref "C37") (pin "1") (pinfunction "1_1") (pintype "passive"))
      (node (ref "J13") (pin "P$3") (pinfunction "3_P$3") (pintype "bidirectional"))
      (node (ref "R15") (pin "1") (pinfunction "1_1") (pintype "passive"))
      (node (ref "U3") (pin "P11") (pinfunction "BIASM_P11") (pintype "bidirectional"))
    )
    (net (code "34") (name "Net-(J14-1)") (class "Default")
      (node (ref "J14") (pin "P$1") (pinfunction "1_P$1") (pintype "bidirectional"))
      (node (ref "PR3") (pin "1") (pinfunction "1_1") (pintype "passive"))
    )
    (net (code "35") (name "Net-(J14-2)") (class "Default")
      (node (ref "J14") (pin "P$2") (pinfunction "2_P$2") (pintype "bidirectional"))
      (node (ref "R16") (pin "1") (pinfunction "1_1") (pintype "passive"))
      (node (ref "R17") (pin "1") (pinfunction "1_1") (pintype "passive"))
    )
    (net (code "36") (name "Net-(R13-Pad2)") (class "Default")
      (node (ref "R13") (pin "2") (pinfunction "2_2") (pintype "passive"))
      (node (ref "VR3") (pin "B") (pinfunction "B_B") (pintype "passive"))
      (node (ref "VR3") (pin "C") (pinfunction "C_C") (pintype "passive"))
    )
    (net (code "37") (name "Net-(R24-Pad2)") (class "Default")
      (node (ref "R24") (pin "2") (pinfunction "2_2") (pintype "passive"))
      (node (ref "VR5") (pin "B") (pinfunction "B_B") (pintype "passive"))
      (node (ref "VR5") (pin "C") (pinfunction "C_C") (pintype "passive"))
    )
    (net (code "38") (name "Net-(R56-Pad2)") (class "Default")
      (node (ref "R56") (pin "2") (pinfunction "2_2") (pintype "passive"))
      (node (ref "VR1") (pin "B") (pinfunction "B_B") (pintype "passive"))
      (node (ref "VR1") (pin "C") (pinfunction "C_C") (pintype "passive"))
    )
    (net (code "39") (name "Net-(U1-BIASP)") (class "Default")
      (node (ref "C9") (pin "2") (pinfunction "2_2") (pintype "passive"))
      (node (ref "R44") (pin "2") (pinfunction "2_2") (pintype "passive"))
      (node (ref "U1") (pin "P12") (pinfunction "BIASP_P12") (pintype "bidirectional"))
    )
    (net (code "40") (name "Net-(U1-COMP)") (class "Default")
      (node (ref "C8") (pin "2") (pinfunction "2_2") (pintype "passive"))
      (node (ref "U1") (pin "P6") (pinfunction "COMP_P6") (pintype "bidirectional"))
    )
    (net (code "41") (name "Net-(U1-IN+)") (class "Default")
      (node (ref "C1") (pin "2") (pinfunction "2_2") (pintype "passive"))
      (node (ref "R1") (pin "1") (pinfunction "1_1") (pintype "passive"))
      (node (ref "R2") (pin "1") (pinfunction "1_1") (pintype "passive"))
      (node (ref "U1") (pin "P4") (pinfunction "IN+_P4") (pintype "bidirectional"))
    )
    (net (code "42") (name "Net-(U1-IN-)") (class "Default")
      (node (ref "R55") (pin "1") (pinfunction "1_1") (pintype "passive"))
      (node (ref "U1") (pin "P5") (pinfunction "IN-_P5") (pintype "bidirectional"))
      (node (ref "VR1") (pin "A") (pinfunction "A_A") (pintype "passive"))
    )
    (net (code "43") (name "Net-(U1-MUTE)") (class "Default")
      (node (ref "C6") (pin "+") (pinfunction "+_+") (pintype "passive"))
      (node (ref "R52") (pin "2") (pinfunction "2_2") (pintype "passive"))
      (node (ref "U1") (pin "P2") (pinfunction "MUTE_P2") (pintype "bidirectional"))
    )
    (net (code "44") (name "Net-(U1-NOUT)") (class "Default")
      (node (ref "R48") (pin "2") (pinfunction "2_2") (pintype "passive"))
      (node (ref "U1") (pin "P14") (pinfunction "NOUT_P14") (pintype "bidirectional"))
    )
    (net (code "45") (name "Net-(U1-POUT)") (class "Default")
      (node (ref "R47") (pin "2") (pinfunction "2_2") (pintype "passive"))
      (node (ref "U1") (pin "P13") (pinfunction "POUT_P13") (pintype "bidirectional"))
    )
    (net (code "46") (name "Net-(U2-BIASP)") (class "Default")
      (node (ref "C20") (pin "2") (pinfunction "2_2") (pintype "passive"))
      (node (ref "R3") (pin "2") (pinfunction "2_2") (pintype "passive"))
      (node (ref "U2") (pin "P12") (pinfunction "BIASP_P12") (pintype "bidirectional"))
    )
    (net (code "47") (name "Net-(U2-COMP)") (class "Default")
      (node (ref "C22") (pin "2") (pinfunction "2_2") (pintype "passive"))
      (node (ref "U2") (pin "P6") (pinfunction "COMP_P6") (pintype "bidirectional"))
    )
    (net (code "48") (name "Net-(U2-IN+)") (class "Default")
      (node (ref "C29") (pin "2") (pinfunction "2_2") (pintype "passive"))
      (node (ref "R10") (pin "1") (pinfunction "1_1") (pintype "passive"))
      (node (ref "R11") (pin "1") (pinfunction "1_1") (pintype "passive"))
      (node (ref "U2") (pin "P4") (pinfunction "IN+_P4") (pintype "bidirectional"))
    )
    (net (code "49") (name "Net-(U2-IN-)") (class "Default")
      (node (ref "R12") (pin "1") (pinfunction "1_1") (pintype "passive"))
      (node (ref "U2") (pin "P5") (pinfunction "IN-_P5") (pintype "bidirectional"))
      (node (ref "VR3") (pin "A") (pinfunction "A_A") (pintype "passive"))
    )
    (net (code "50") (name "Net-(U2-MUTE)") (class "Default")
      (node (ref "C28") (pin "+") (pinfunction "+_+") (pintype "passive"))
      (node (ref "R9") (pin "2") (pinfunction "2_2") (pintype "passive"))
      (node (ref "U2") (pin "P2") (pinfunction "MUTE_P2") (pintype "bidirectional"))
    )
    (net (code "51") (name "Net-(U2-NOUT)") (class "Default")
      (node (ref "R7") (pin "2") (pinfunction "2_2") (pintype "passive"))
      (node (ref "U2") (pin "P14") (pinfunction "NOUT_P14") (pintype "bidirectional"))
    )
    (net (code "52") (name "Net-(U2-POUT)") (class "Default")
      (node (ref "R6") (pin "2") (pinfunction "2_2") (pintype "passive"))
      (node (ref "U2") (pin "P13") (pinfunction "POUT_P13") (pintype "bidirectional"))
    )
    (net (code "53") (name "Net-(U3-BIASP)") (class "Default")
      (node (ref "C35") (pin "2") (pinfunction "2_2") (pintype "passive"))
      (node (ref "R14") (pin "2") (pinfunction "2_2") (pintype "passive"))
      (node (ref "U3") (pin "P12") (pinfunction "BIASP_P12") (pintype "bidirectional"))
    )
    (net (code "54") (name "Net-(U3-COMP)") (class "Default")
      (node (ref "C37") (pin "2") (pinfunction "2_2") (pintype "passive"))
      (node (ref "U3") (pin "P6") (pinfunction "COMP_P6") (pintype "bidirectional"))
    )
    (net (code "55") (name "Net-(U3-IN+)") (class "Default")
      (node (ref "C44") (pin "2") (pinfunction "2_2") (pintype "passive"))
      (node (ref "R21") (pin "1") (pinfunction "1_1") (pintype "passive"))
      (node (ref "R22") (pin "1") (pinfunction "1_1") (pintype "passive"))
      (node (ref "U3") (pin "P4") (pinfunction "IN+_P4") (pintype "bidirectional"))
    )
    (net (code "56") (name "Net-(U3-IN-)") (class "Default")
      (node (ref "R23") (pin "1") (pinfunction "1_1") (pintype "passive"))
      (node (ref "U3") (pin "P5") (pinfunction "IN-_P5") (pintype "bidirectional"))
      (node (ref "VR5") (pin "A") (pinfunction "A_A") (pintype "passive"))
    )
    (net (code "57") (name "Net-(U3-MUTE)") (class "Default")
      (node (ref "C43") (pin "+") (pinfunction "+_+") (pintype "passive"))
      (node (ref "R20") (pin "2") (pinfunction "2_2") (pintype "passive"))
      (node (ref "U3") (pin "P2") (pinfunction "MUTE_P2") (pintype "bidirectional"))
    )
    (net (code "58") (name "Net-(U3-NOUT)") (class "Default")
      (node (ref "R18") (pin "2") (pinfunction "2_2") (pintype "passive"))
      (node (ref "U3") (pin "P14") (pinfunction "NOUT_P14") (pintype "bidirectional"))
    )
    (net (code "59") (name "Net-(U3-POUT)") (class "Default")
      (node (ref "R17") (pin "2") (pinfunction "2_2") (pintype "passive"))
      (node (ref "U3") (pin "P13") (pinfunction "POUT_P13") (pintype "bidirectional"))
    )
    (net (code "60") (name "V+") (class "Default")
      (node (ref "C11") (pin "1") (pinfunction "1_1") (pintype "passive"))
      (node (ref "C12") (pin "+") (pinfunction "+_+") (pintype "passive"))
      (node (ref "C17") (pin "+") (pinfunction "+_+") (pintype "passive"))
      (node (ref "C19") (pin "1") (pinfunction "1_1") (pintype "passive"))
      (node (ref "C23") (pin "+") (pinfunction "+_+") (pintype "passive"))
      (node (ref "C25") (pin "1") (pinfunction "1_1") (pintype "passive"))
      (node (ref "C32") (pin "+") (pinfunction "+_+") (pintype "passive"))
      (node (ref "C34") (pin "1") (pinfunction "1_1") (pintype "passive"))
      (node (ref "C38") (pin "+") (pinfunction "+_+") (pintype "passive"))
      (node (ref "C4") (pin "+") (pinfunction "+_+") (pintype "passive"))
      (node (ref "C40") (pin "1") (pinfunction "1_1") (pintype "passive"))
      (node (ref "C5") (pin "1") (pinfunction "1_1") (pintype "passive"))
      (node (ref "J12") (pin "P$1") (pinfunction "1_P$1") (pintype "bidirectional"))
      (node (ref "J2") (pin "P$4") (pinfunction "4_P$4") (pintype "passive"))
      (node (ref "J6") (pin "P$1") (pinfunction "1_P$1") (pintype "bidirectional"))
      (node (ref "J9") (pin "P$1") (pinfunction "1_P$1") (pintype "bidirectional"))
      (node (ref "U1") (pin "P15") (pinfunction "+VCC_P15") (pintype "passive"))
      (node (ref "U2") (pin "P15") (pinfunction "+VCC_P15") (pintype "passive"))
      (node (ref "U3") (pin "P15") (pinfunction "+VCC_P15") (pintype "passive"))
    )
    (net (code "61") (name "V-") (class "Default")
      (node (ref "C13") (pin "2") (pinfunction "2_2") (pintype "passive"))
      (node (ref "C14") (pin "-") (pinfunction "-_-") (pintype "passive"))
      (node (ref "C16") (pin "-") (pinfunction "-_-") (pintype "passive"))
      (node (ref "C18") (pin "2") (pinfunction "2_2") (pintype "passive"))
      (node (ref "C2") (pin "-") (pinfunction "-_-") (pintype "passive"))
      (node (ref "C24") (pin "-") (pinfunction "-_-") (pintype "passive"))
      (node (ref "C26") (pin "2") (pinfunction "2_2") (pintype "passive"))
      (node (ref "C3") (pin "2") (pinfunction "2_2") (pintype "passive"))
      (node (ref "C31") (pin "-") (pinfunction "-_-") (pintype "passive"))
      (node (ref "C33") (pin "2") (pinfunction "2_2") (pintype "passive"))
      (node (ref "C39") (pin "-") (pinfunction "-_-") (pintype "passive"))
      (node (ref "C41") (pin "2") (pinfunction "2_2") (pintype "passive"))
      (node (ref "J11") (pin "P$3") (pinfunction "3_P$3") (pintype "bidirectional"))
      (node (ref "J14") (pin "P$3") (pinfunction "3_P$3") (pintype "bidirectional"))
      (node (ref "J2") (pin "P$3") (pinfunction "3_P$3") (pintype "passive"))
      (node (ref "J8") (pin "P$3") (pinfunction "3_P$3") (pintype "bidirectional"))
      (node (ref "U1") (pin "P10") (pinfunction "-VEE_P10") (pintype "power_in"))
      (node (ref "U2") (pin "P10") (pinfunction "-VEE_P10") (pintype "power_in"))
      (node (ref "U3") (pin "P10") (pinfunction "-VEE_P10") (pintype "power_in"))
    )
  )
)
